# DSO_Clock.net
KiCad netlist of a schematic drawn in Altium Designer
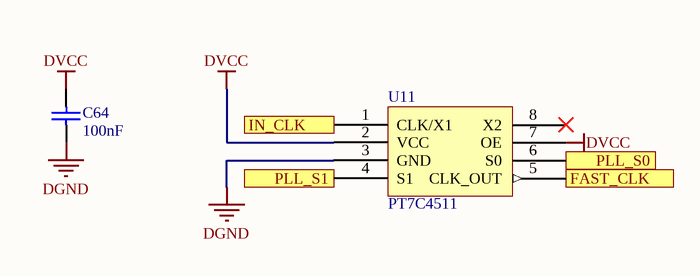
[diagram p0: DSO_Clock.SchDoc]

(export (version "E")
  (design (tool "Eeschema 10.0.6"))
  (components
    (comp (ref "C64")
      (value "100nF")
      (footprint "0805C")
      (description "Capacitor")
      (fields (field (name "REVIEWED BY") "RM - 2018/08/05"))
      (libsource (lib "DSO") (part "C"))
    )
    (comp (ref "U11")
      (value "PT7C4511")
      (footprint "SOIC-8")
      (description "PLL Clock Multiplier")
      (fields (field (name "REVIEWED BY") "RM - 2018/08/05"))
      (libsource (lib "DSO") (part "PT7C4511"))
    )
  )
  (nets
    (net (code "1") (name "/FAST_CLK") (class "Default")
      (node (ref "U11") (pin "5") (pinfunction "CLK_OUT_5") (pintype "output"))
    )
    (net (code "2") (name "/IN_CLK") (class "Default")
      (node (ref "U11") (pin "1") (pinfunction "CLK/X1_1") (pintype "passive"))
    )
    (net (code "3") (name "/PLL_S0") (class "Default")
      (node (ref "U11") (pin "6") (pinfunction "S0_6") (pintype "passive"))
    )
    (net (code "4") (name "/PLL_S1") (class "Default")
      (node (ref "U11") (pin "4") (pinfunction "S1_4") (pintype "passive"))
    )
    (net (code "5") (name "DGND") (class "Default")
      (node (ref "C64") (pin "2") (pinfunction "2_2") (pintype "passive"))
      (node (ref "U11") (pin "3") (pinfunction "GND_3") (pintype "passive"))
    )
    (net (code "6") (name "DVCC") (class "Default")
      (node (ref "C64") (pin "1") (pinfunction "1_1") (pintype "passive"))
      (node (ref "U11") (pin "2") (pinfunction "VCC_2") (pintype "passive"))
      (node (ref "U11") (pin "7") (pinfunction "OE_7") (pintype "passive"))
    )
    (net (code "7") (name "unconnected-(U11-X2-Pad8)") (class "Default")
      (node (ref "U11") (pin "8") (pinfunction "X2_8") (pintype "passive+no_connect"))
    )
  )
)
